# Solenoid_Board.net
KiCad netlist of a schematic drawn in EAGLE
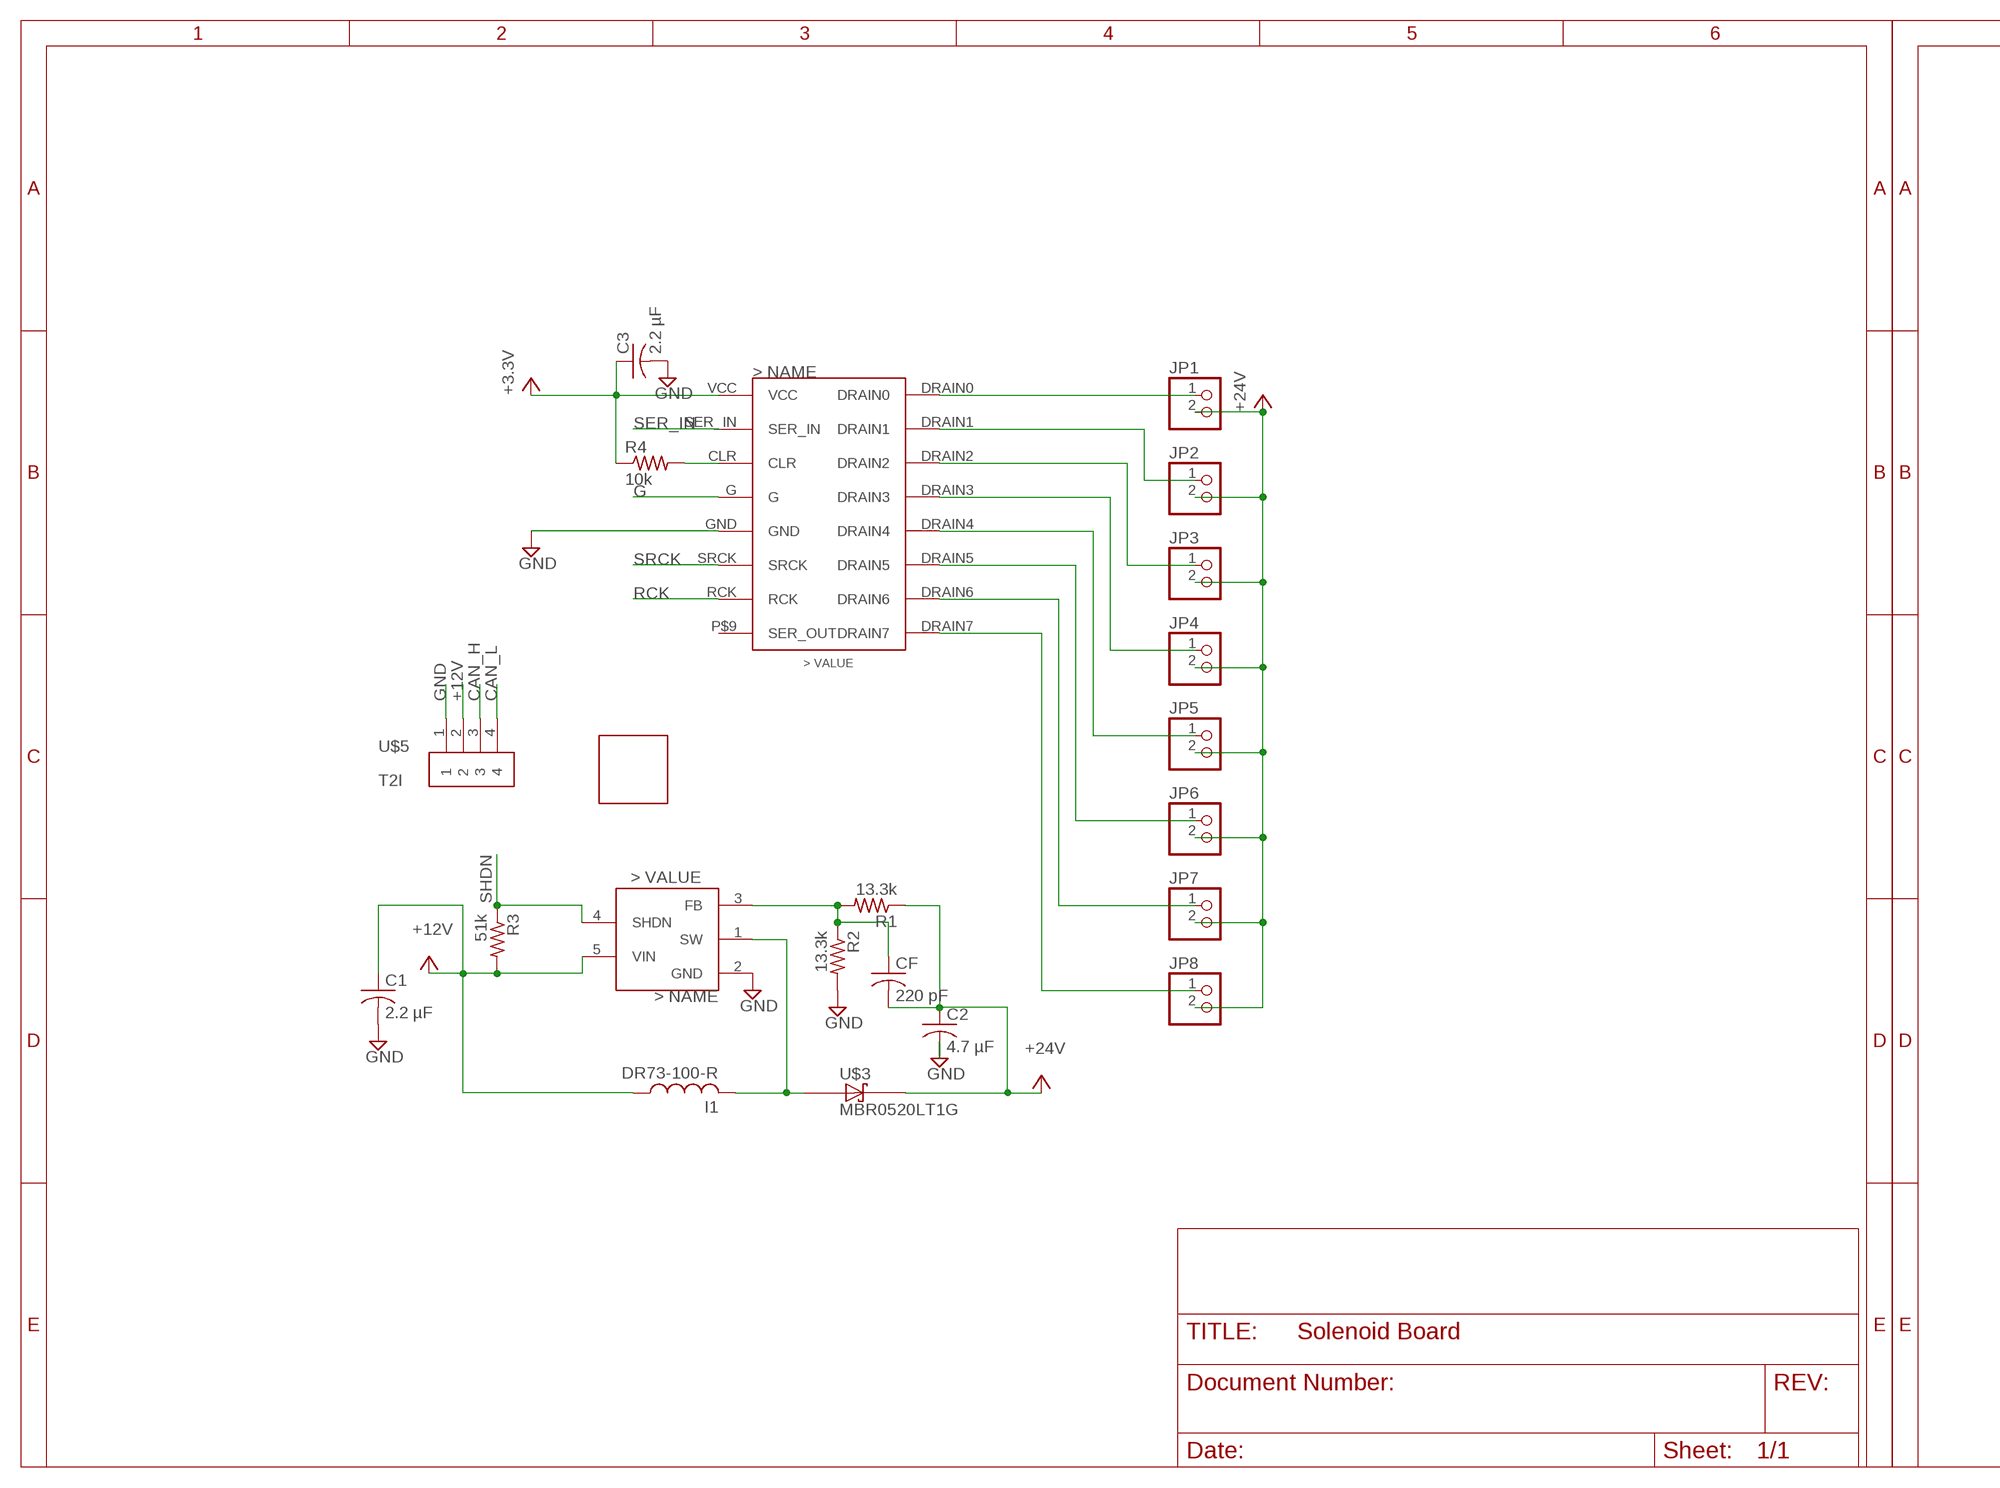
[diagram p0: schematic, sheet 1, part 1 of 2]
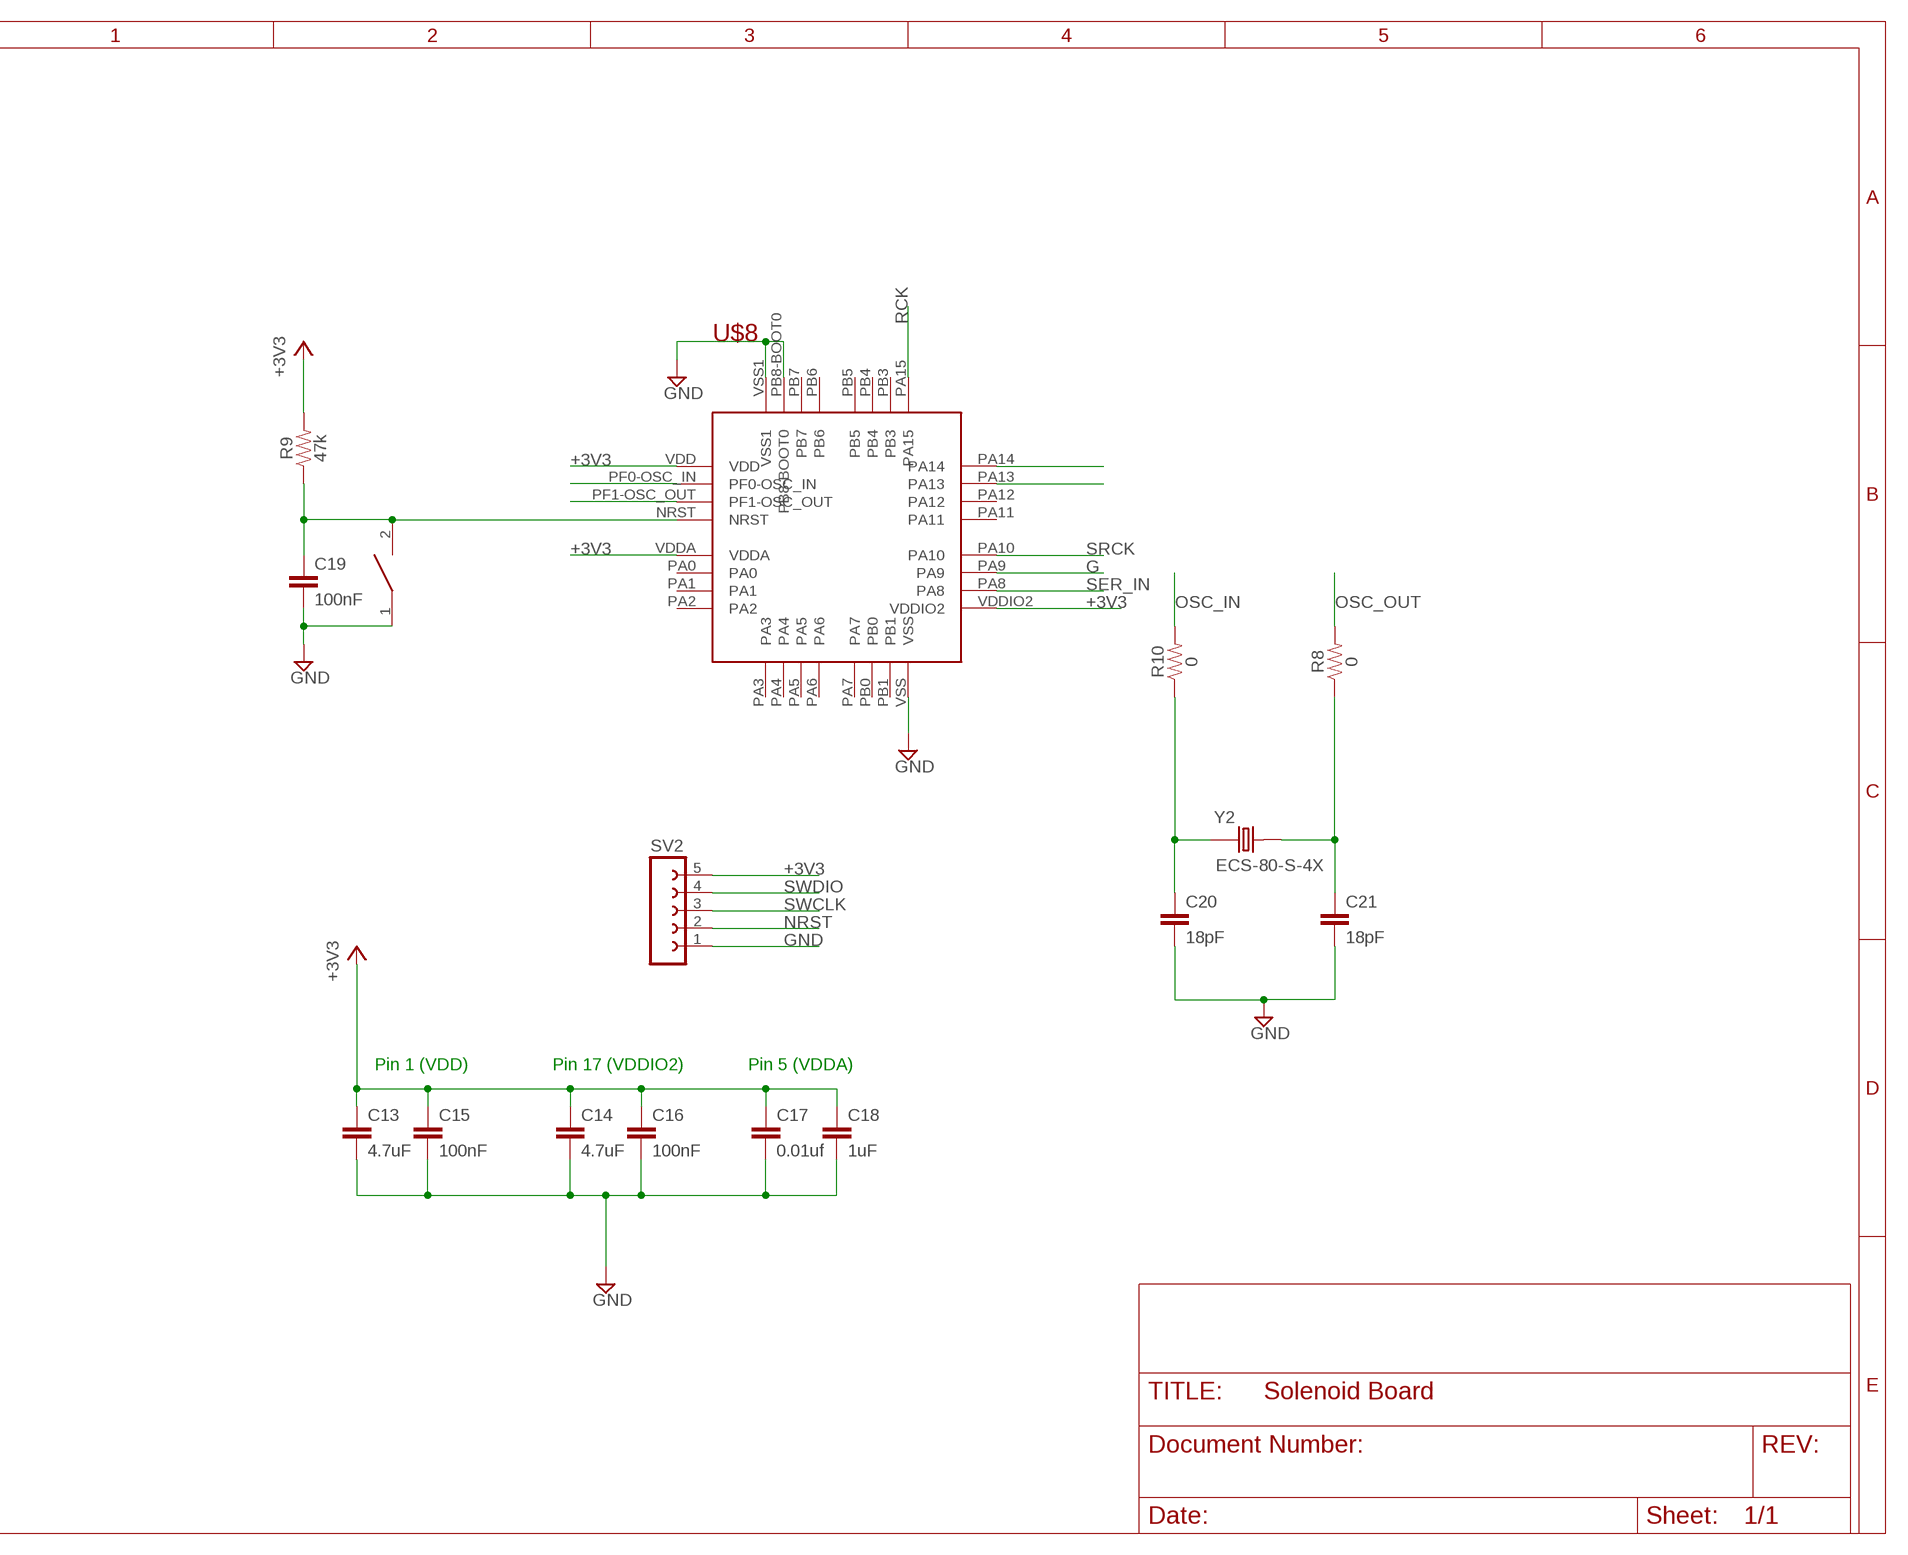
[diagram p1: schematic, sheet 1, part 2 of 2]

(export (version "E")
  (design (tool "Eeschema 10.0.6"))
  (components
    (comp (ref "C1")
      (value "2.2 µF")
      (footprint "eagle-import:C0805")
      (libsource (lib "eagle-import") (part "C-USC0805"))
    )
    (comp (ref "C2")
      (value "4.7 µF")
      (footprint "eagle-import:C0805")
      (libsource (lib "eagle-import") (part "C-USC0805"))
    )
    (comp (ref "C3")
      (value "2.2 µF")
      (footprint "eagle-import:C0805")
      (libsource (lib "eagle-import") (part "C-USC0805"))
    )
    (comp (ref "C13")
      (value "4.7uF")
      (footprint "eagle-import:0603")
      (libsource (lib "eagle-import") (part "4.7UF0603"))
    )
    (comp (ref "C14")
      (value "4.7uF")
      (footprint "eagle-import:0603")
      (libsource (lib "eagle-import") (part "4.7UF0603"))
    )
    (comp (ref "C15")
      (value "100nF")
      (footprint "eagle-import:0603")
      (libsource (lib "eagle-import") (part "4.7UF0603"))
    )
    (comp (ref "C16")
      (value "100nF")
      (footprint "eagle-import:0603")
      (libsource (lib "eagle-import") (part "4.7UF0603"))
    )
    (comp (ref "C17")
      (value "0.01uf")
      (footprint "eagle-import:0603")
      (libsource (lib "eagle-import") (part "4.7UF0603"))
    )
    (comp (ref "C18")
      (value "1uF")
      (footprint "eagle-import:0603")
      (libsource (lib "eagle-import") (part "4.7UF0603"))
    )
    (comp (ref "C19")
      (value "100nF")
      (footprint "eagle-import:0603")
      (libsource (lib "eagle-import") (part "4.7UF0603"))
    )
    (comp (ref "C20")
      (value "18pF")
      (footprint "eagle-import:0603")
      (libsource (lib "eagle-import") (part "4.7UF0603"))
    )
    (comp (ref "C21")
      (value "18pF")
      (footprint "eagle-import:0603")
      (libsource (lib "eagle-import") (part "4.7UF0603"))
    )
    (comp (ref "CF")
      (value "220 pF")
      (footprint "eagle-import:C0805")
      (libsource (lib "eagle-import") (part "C-USC0805"))
    )
    (comp (ref "I1")
      (value "DR73-100-R")
      (footprint "eagle-import:DR73-100-R")
      (libsource (lib "eagle-import") (part "DR73-100-R"))
    )
    (comp (ref "JP1")
      (value "PINHD-1X2")
      (footprint "eagle-import:1X02")
      (libsource (lib "eagle-import") (part "PINHD-1X2"))
    )
    (comp (ref "JP2")
      (value "PINHD-1X2")
      (footprint "eagle-import:1X02")
      (libsource (lib "eagle-import") (part "PINHD-1X2"))
    )
    (comp (ref "JP3")
      (value "PINHD-1X2")
      (footprint "eagle-import:1X02")
      (libsource (lib "eagle-import") (part "PINHD-1X2"))
    )
    (comp (ref "JP4")
      (value "PINHD-1X2")
      (footprint "eagle-import:1X02")
      (libsource (lib "eagle-import") (part "PINHD-1X2"))
    )
    (comp (ref "JP5")
      (value "PINHD-1X2")
      (footprint "eagle-import:1X02")
      (libsource (lib "eagle-import") (part "PINHD-1X2"))
    )
    (comp (ref "JP6")
      (value "PINHD-1X2")
      (footprint "eagle-import:1X02")
      (libsource (lib "eagle-import") (part "PINHD-1X2"))
    )
    (comp (ref "JP7")
      (value "PINHD-1X2")
      (footprint "eagle-import:1X02")
      (libsource (lib "eagle-import") (part "PINHD-1X2"))
    )
    (comp (ref "JP8")
      (value "PINHD-1X2")
      (footprint "eagle-import:1X02")
      (libsource (lib "eagle-import") (part "PINHD-1X2"))
    )
    (comp (ref "R1")
      (value "13.3k")
      (footprint "eagle-import:R0603")
      (libsource (lib "eagle-import") (part "R-US_R0603"))
    )
    (comp (ref "R2")
      (value "13.3k")
      (footprint "eagle-import:R0603")
      (libsource (lib "eagle-import") (part "R-US_R0603"))
    )
    (comp (ref "R3")
      (value "51k")
      (footprint "eagle-import:R0603")
      (libsource (lib "eagle-import") (part "R-US_R0603"))
    )
    (comp (ref "R4")
      (value "10k")
      (footprint "eagle-import:R0603")
      (libsource (lib "eagle-import") (part "R-US_R0603"))
    )
    (comp (ref "R8")
      (value "0")
      (footprint "eagle-import:0603")
      (libsource (lib "eagle-import") (part "1KOHM-0603-1/10W-1%"))
    )
    (comp (ref "R9")
      (value "47k")
      (footprint "eagle-import:0603")
      (libsource (lib "eagle-import") (part "1KOHM-0603-1/10W-1%"))
    )
    (comp (ref "R10")
      (value "0")
      (footprint "eagle-import:0603")
      (libsource (lib "eagle-import") (part "1KOHM-0603-1/10W-1%"))
    )
    (comp (ref "RESET1")
      (value "SWITCH")
      (footprint "eagle-import:SW_2512")
      (libsource (lib "eagle-import") (part "SWITCH"))
    )
    (comp (ref "SV2")
      (value "FE05-1")
      (footprint "eagle-import:FE05-1")
      (libsource (lib "eagle-import") (part "FE05-1"))
    )
    (comp (ref "U$1")
      (value "SHIFT_REGISTER")
      (footprint "eagle-import:SHIFT_REGISTER")
      (libsource (lib "eagle-import") (part "SHIFT_REGISTER"))
    )
    (comp (ref "U$2")
      (value "LM27313")
      (footprint "eagle-import:SOT95P300X145-5")
      (libsource (lib "eagle-import") (part "LM27313"))
    )
    (comp (ref "U$3")
      (value "MBR0520LT1G")
      (footprint "eagle-import:SOD3716X135")
      (libsource (lib "eagle-import") (part "MBR0520LT1G"))
    )
    (comp (ref "U$5")
      (value "T2I")
      (footprint "eagle-import:T2I")
      (libsource (lib "eagle-import") (part "T2I"))
    )
    (comp (ref "U$6")
      (value "BOARDPNE")
      (footprint "eagle-import:PNE")
      (libsource (lib "eagle-import") (part "BOARDPNE"))
    )
    (comp (ref "U$8")
      (value "STM32F042K6T6")
      (footprint "eagle-import:STM32F042K6T6")
      (libsource (lib "eagle-import") (part "STM32F042K6T6"))
    )
    (comp (ref "Y2")
      (value "ECS-80-S-4X")
      (footprint "eagle-import:XTAL_ECS-80-S-4X")
      (fields (field (name "DIGI-KEY_PART_NUMBER") "X1057-ND") (field (name "MF") "ECS International"))
      (libsource (lib "eagle-import") (part "ECS-80-S-4X"))
    )
  )
  (nets
    (net (code "1") (name "+3.3V") (class "Default")
      (node (ref "C3") (pin "1") (pinfunction "1_1") (pintype "passive"))
      (node (ref "R4") (pin "1") (pinfunction "1_1") (pintype "passive"))
      (node (ref "U$1") (pin "VCC") (pinfunction "VCC_VCC") (pintype "bidirectional"))
    )
    (net (code "2") (name "+3V3") (class "Default")
      (node (ref "C13") (pin "1") (pinfunction "1_1") (pintype "passive"))
      (node (ref "C14") (pin "1") (pinfunction "1_1") (pintype "passive"))
      (node (ref "C15") (pin "1") (pinfunction "1_1") (pintype "passive"))
      (node (ref "C16") (pin "1") (pinfunction "1_1") (pintype "passive"))
      (node (ref "C17") (pin "1") (pinfunction "1_1") (pintype "passive"))
      (node (ref "C18") (pin "1") (pinfunction "1_1") (pintype "passive"))
      (node (ref "R9") (pin "2") (pinfunction "2_2") (pintype "passive"))
      (node (ref "SV2") (pin "5") (pinfunction "5_5") (pintype "passive"))
      (node (ref "U$8") (pin "VDD") (pinfunction "VDD_VDD") (pintype "bidirectional"))
      (node (ref "U$8") (pin "VDDA") (pinfunction "VDDA_VDDA") (pintype "bidirectional"))
      (node (ref "U$8") (pin "VDDIO2") (pinfunction "VDDIO2_VDDIO2") (pintype "bidirectional"))
    )
    (net (code "3") (name "+12V") (class "Default")
      (node (ref "C1") (pin "1") (pinfunction "1_1") (pintype "passive"))
      (node (ref "I1") (pin "1") (pinfunction "1_1") (pintype "passive"))
      (node (ref "R3") (pin "2") (pinfunction "2_2") (pintype "passive"))
      (node (ref "U$2") (pin "5") (pinfunction "VIN_5") (pintype "bidirectional"))
      (node (ref "U$5") (pin "2") (pinfunction "2_2") (pintype "bidirectional"))
    )
    (net (code "4") (name "+24V") (class "Default")
      (node (ref "C2") (pin "1") (pinfunction "1_1") (pintype "passive"))
      (node (ref "CF") (pin "2") (pinfunction "2_2") (pintype "passive"))
      (node (ref "JP1") (pin "2") (pinfunction "2_2") (pintype "passive"))
      (node (ref "JP2") (pin "2") (pinfunction "2_2") (pintype "passive"))
      (node (ref "JP3") (pin "2") (pinfunction "2_2") (pintype "passive"))
      (node (ref "JP4") (pin "2") (pinfunction "2_2") (pintype "passive"))
      (node (ref "JP5") (pin "2") (pinfunction "2_2") (pintype "passive"))
      (node (ref "JP6") (pin "2") (pinfunction "2_2") (pintype "passive"))
      (node (ref "JP7") (pin "2") (pinfunction "2_2") (pintype "passive"))
      (node (ref "JP8") (pin "2") (pinfunction "2_2") (pintype "passive"))
      (node (ref "R1") (pin "1") (pinfunction "1_1") (pintype "passive"))
      (node (ref "U$3") (pin "2") (pinfunction "C_2") (pintype "passive"))
    )
    (net (code "5") (name "/CAN_H") (class "Default")
      (node (ref "U$5") (pin "3") (pinfunction "3_3") (pintype "bidirectional"))
    )
    (net (code "6") (name "/CAN_L") (class "Default")
      (node (ref "U$5") (pin "4") (pinfunction "4_4") (pintype "bidirectional"))
    )
    (net (code "7") (name "/G") (class "Default")
      (node (ref "U$1") (pin "G") (pinfunction "G_G") (pintype "bidirectional"))
      (node (ref "U$8") (pin "PA9") (pinfunction "PA9_PA9") (pintype "bidirectional"))
    )
    (net (code "8") (name "/NRST") (class "Default")
      (node (ref "C19") (pin "1") (pinfunction "1_1") (pintype "passive"))
      (node (ref "R9") (pin "1") (pinfunction "1_1") (pintype "passive"))
      (node (ref "RESET1") (pin "2") (pinfunction "P$2_2") (pintype "bidirectional"))
      (node (ref "SV2") (pin "2") (pinfunction "2_2") (pintype "passive"))
      (node (ref "U$8") (pin "NRST") (pinfunction "NRST_NRST") (pintype "bidirectional"))
    )
    (net (code "9") (name "/OSC_IN") (class "Default")
      (node (ref "R10") (pin "2") (pinfunction "2_2") (pintype "passive"))
      (node (ref "U$8") (pin "PF0-OSC_IN") (pinfunction "PF0-OSC_IN_PF0-OSC_IN") (pintype "bidirectional"))
    )
    (net (code "10") (name "/OSC_OUT") (class "Default")
      (node (ref "R8") (pin "2") (pinfunction "2_2") (pintype "passive"))
      (node (ref "U$8") (pin "PF1-OSC_OUT") (pinfunction "PF1-OSC_OUT_PF1-OSC_OUT") (pintype "bidirectional"))
    )
    (net (code "11") (name "/RCK") (class "Default")
      (node (ref "U$1") (pin "RCK") (pinfunction "RCK_RCK") (pintype "bidirectional"))
      (node (ref "U$8") (pin "PA15") (pinfunction "PA15_PA15") (pintype "bidirectional"))
    )
    (net (code "12") (name "/SER_IN") (class "Default")
      (node (ref "U$1") (pin "SER_IN") (pinfunction "SER_IN_SER_IN") (pintype "bidirectional"))
      (node (ref "U$8") (pin "PA8") (pinfunction "PA8_PA8") (pintype "bidirectional"))
    )
    (net (code "13") (name "/SHDN") (class "Default")
      (node (ref "R3") (pin "1") (pinfunction "1_1") (pintype "passive"))
      (node (ref "U$2") (pin "4") (pinfunction "SHDN_4") (pintype "bidirectional"))
    )
    (net (code "14") (name "/SRCK") (class "Default")
      (node (ref "U$1") (pin "SRCK") (pinfunction "SRCK_SRCK") (pintype "bidirectional"))
      (node (ref "U$8") (pin "PA10") (pinfunction "PA10_PA10") (pintype "bidirectional"))
    )
    (net (code "15") (name "/SWCLK") (class "Default")
      (node (ref "SV2") (pin "3") (pinfunction "3_3") (pintype "passive"))
      (node (ref "U$8") (pin "PA14") (pinfunction "PA14_PA14") (pintype "bidirectional"))
    )
    (net (code "16") (name "/SWDIO") (class "Default")
      (node (ref "SV2") (pin "4") (pinfunction "4_4") (pintype "passive"))
      (node (ref "U$8") (pin "PA13") (pinfunction "PA13_PA13") (pintype "bidirectional"))
    )
    (net (code "17") (name "GND") (class "Default")
      (node (ref "C1") (pin "2") (pinfunction "2_2") (pintype "passive"))
      (node (ref "C13") (pin "2") (pinfunction "2_2") (pintype "passive"))
      (node (ref "C14") (pin "2") (pinfunction "2_2") (pintype "passive"))
      (node (ref "C15") (pin "2") (pinfunction "2_2") (pintype "passive"))
      (node (ref "C16") (pin "2") (pinfunction "2_2") (pintype "passive"))
      (node (ref "C17") (pin "2") (pinfunction "2_2") (pintype "passive"))
      (node (ref "C18") (pin "2") (pinfunction "2_2") (pintype "passive"))
      (node (ref "C19") (pin "2") (pinfunction "2_2") (pintype "passive"))
      (node (ref "C2") (pin "2") (pinfunction "2_2") (pintype "passive"))
      (node (ref "C20") (pin "2") (pinfunction "2_2") (pintype "passive"))
      (node (ref "C21") (pin "2") (pinfunction "2_2") (pintype "passive"))
      (node (ref "C3") (pin "2") (pinfunction "2_2") (pintype "passive"))
      (node (ref "R2") (pin "2") (pinfunction "2_2") (pintype "passive"))
      (node (ref "RESET1") (pin "1") (pinfunction "P$1_1") (pintype "bidirectional"))
      (node (ref "SV2") (pin "1") (pinfunction "1_1") (pintype "passive"))
      (node (ref "U$1") (pin "GND") (pinfunction "GND_GND") (pintype "bidirectional"))
      (node (ref "U$2") (pin "2") (pinfunction "GND_2") (pintype "bidirectional"))
      (node (ref "U$5") (pin "1") (pinfunction "1_1") (pintype "bidirectional"))
      (node (ref "U$8") (pin "PB8-BOOT0") (pinfunction "PB8-BOOT0_PB8-BOOT0") (pintype "bidirectional"))
      (node (ref "U$8") (pin "VSS") (pinfunction "VSS_VSS") (pintype "bidirectional"))
      (node (ref "U$8") (pin "VSS1") (pinfunction "VSS1_VSS1") (pintype "bidirectional"))
    )
    (net (code "18") (name "Net-(C20-Pad1)") (class "Default")
      (node (ref "C20") (pin "1") (pinfunction "1_1") (pintype "passive"))
      (node (ref "R10") (pin "1") (pinfunction "1_1") (pintype "passive"))
      (node (ref "Y2") (pin "1") (pinfunction "1_1") (pintype "passive"))
    )
    (net (code "19") (name "Net-(C21-Pad1)") (class "Default")
      (node (ref "C21") (pin "1") (pinfunction "1_1") (pintype "passive"))
      (node (ref "R8") (pin "1") (pinfunction "1_1") (pintype "passive"))
      (node (ref "Y2") (pin "2") (pinfunction "2_2") (pintype "passive"))
    )
    (net (code "20") (name "Net-(JP1-Pad1)") (class "Default")
      (node (ref "JP1") (pin "1") (pinfunction "1_1") (pintype "passive"))
      (node (ref "U$1") (pin "DRAIN0") (pinfunction "DRAIN0_DRAIN0") (pintype "bidirectional"))
    )
    (net (code "21") (name "Net-(JP2-Pad1)") (class "Default")
      (node (ref "JP2") (pin "1") (pinfunction "1_1") (pintype "passive"))
      (node (ref "U$1") (pin "DRAIN1") (pinfunction "DRAIN1_DRAIN1") (pintype "bidirectional"))
    )
    (net (code "22") (name "Net-(JP3-Pad1)") (class "Default")
      (node (ref "JP3") (pin "1") (pinfunction "1_1") (pintype "passive"))
      (node (ref "U$1") (pin "DRAIN2") (pinfunction "DRAIN2_DRAIN2") (pintype "bidirectional"))
    )
    (net (code "23") (name "Net-(JP4-Pad1)") (class "Default")
      (node (ref "JP4") (pin "1") (pinfunction "1_1") (pintype "passive"))
      (node (ref "U$1") (pin "DRAIN3") (pinfunction "DRAIN3_DRAIN3") (pintype "bidirectional"))
    )
    (net (code "24") (name "Net-(JP5-Pad1)") (class "Default")
      (node (ref "JP5") (pin "1") (pinfunction "1_1") (pintype "passive"))
      (node (ref "U$1") (pin "DRAIN4") (pinfunction "DRAIN4_DRAIN4") (pintype "bidirectional"))
    )
    (net (code "25") (name "Net-(JP6-Pad1)") (class "Default")
      (node (ref "JP6") (pin "1") (pinfunction "1_1") (pintype "passive"))
      (node (ref "U$1") (pin "DRAIN5") (pinfunction "DRAIN5_DRAIN5") (pintype "bidirectional"))
    )
    (net (code "26") (name "Net-(JP7-Pad1)") (class "Default")
      (node (ref "JP7") (pin "1") (pinfunction "1_1") (pintype "passive"))
      (node (ref "U$1") (pin "DRAIN6") (pinfunction "DRAIN6_DRAIN6") (pintype "bidirectional"))
    )
    (net (code "27") (name "Net-(JP8-Pad1)") (class "Default")
      (node (ref "JP8") (pin "1") (pinfunction "1_1") (pintype "passive"))
      (node (ref "U$1") (pin "DRAIN7") (pinfunction "DRAIN7_DRAIN7") (pintype "bidirectional"))
    )
    (net (code "28") (name "Net-(R4-Pad2)") (class "Default")
      (node (ref "R4") (pin "2") (pinfunction "2_2") (pintype "passive"))
      (node (ref "U$1") (pin "CLR") (pinfunction "CLR_CLR") (pintype "bidirectional"))
    )
    (net (code "29") (name "Net-(U$2-FB)") (class "Default")
      (node (ref "CF") (pin "1") (pinfunction "1_1") (pintype "passive"))
      (node (ref "R1") (pin "2") (pinfunction "2_2") (pintype "passive"))
      (node (ref "R2") (pin "1") (pinfunction "1_1") (pintype "passive"))
      (node (ref "U$2") (pin "3") (pinfunction "FB_3") (pintype "bidirectional"))
    )
    (net (code "30") (name "Net-(U$2-SW)") (class "Default")
      (node (ref "I1") (pin "2") (pinfunction "2_2") (pintype "passive"))
      (node (ref "U$2") (pin "1") (pinfunction "SW_1") (pintype "bidirectional"))
      (node (ref "U$3") (pin "1") (pinfunction "A_1") (pintype "passive"))
    )
    (net (code "31") (name "unconnected-(U$1-SER_OUT-PadP$9)") (class "Default")
      (node (ref "U$1") (pin "P$9") (pinfunction "SER_OUT_P$9") (pintype "bidirectional"))
    )
    (net (code "32") (name "unconnected-(U$8-PadPA0)") (class "Default")
      (node (ref "U$8") (pin "PA0") (pinfunction "PA0_PA0") (pintype "bidirectional"))
    )
    (net (code "33") (name "unconnected-(U$8-PadPA1)") (class "Default")
      (node (ref "U$8") (pin "PA1") (pinfunction "PA1_PA1") (pintype "bidirectional"))
    )
    (net (code "34") (name "unconnected-(U$8-PadPA2)") (class "Default")
      (node (ref "U$8") (pin "PA2") (pinfunction "PA2_PA2") (pintype "bidirectional"))
    )
    (net (code "35") (name "unconnected-(U$8-PadPA3)") (class "Default")
      (node (ref "U$8") (pin "PA3") (pinfunction "PA3_PA3") (pintype "bidirectional"))
    )
    (net (code "36") (name "unconnected-(U$8-PadPA4)") (class "Default")
      (node (ref "U$8") (pin "PA4") (pinfunction "PA4_PA4") (pintype "bidirectional"))
    )
    (net (code "37") (name "unconnected-(U$8-PadPA5)") (class "Default")
      (node (ref "U$8") (pin "PA5") (pinfunction "PA5_PA5") (pintype "bidirectional"))
    )
    (net (code "38") (name "unconnected-(U$8-PadPA6)") (class "Default")
      (node (ref "U$8") (pin "PA6") (pinfunction "PA6_PA6") (pintype "bidirectional"))
    )
    (net (code "39") (name "unconnected-(U$8-PadPA7)") (class "Default")
      (node (ref "U$8") (pin "PA7") (pinfunction "PA7_PA7") (pintype "bidirectional"))
    )
    (net (code "40") (name "unconnected-(U$8-PadPA11)") (class "Default")
      (node (ref "U$8") (pin "PA11") (pinfunction "PA11_PA11") (pintype "bidirectional"))
    )
    (net (code "41") (name "unconnected-(U$8-PadPA12)") (class "Default")
      (node (ref "U$8") (pin "PA12") (pinfunction "PA12_PA12") (pintype "bidirectional"))
    )
    (net (code "42") (name "unconnected-(U$8-PadPB0)") (class "Default")
      (node (ref "U$8") (pin "PB0") (pinfunction "PB0_PB0") (pintype "bidirectional"))
    )
    (net (code "43") (name "unconnected-(U$8-PadPB1)") (class "Default")
      (node (ref "U$8") (pin "PB1") (pinfunction "PB1_PB1") (pintype "bidirectional"))
    )
    (net (code "44") (name "unconnected-(U$8-PadPB3)") (class "Default")
      (node (ref "U$8") (pin "PB3") (pinfunction "PB3_PB3") (pintype "bidirectional"))
    )
    (net (code "45") (name "unconnected-(U$8-PadPB4)") (class "Default")
      (node (ref "U$8") (pin "PB4") (pinfunction "PB4_PB4") (pintype "bidirectional"))
    )
    (net (code "46") (name "unconnected-(U$8-PadPB5)") (class "Default")
      (node (ref "U$8") (pin "PB5") (pinfunction "PB5_PB5") (pintype "bidirectional"))
    )
    (net (code "47") (name "unconnected-(U$8-PadPB6)") (class "Default")
      (node (ref "U$8") (pin "PB6") (pinfunction "PB6_PB6") (pintype "bidirectional"))
    )
    (net (code "48") (name "unconnected-(U$8-PadPB7)") (class "Default")
      (node (ref "U$8") (pin "PB7") (pinfunction "PB7_PB7") (pintype "bidirectional"))
    )
  )
)
